# 20160708_DWC_LSM9DS1.net
KiCad netlist of a schematic drawn in EAGLE
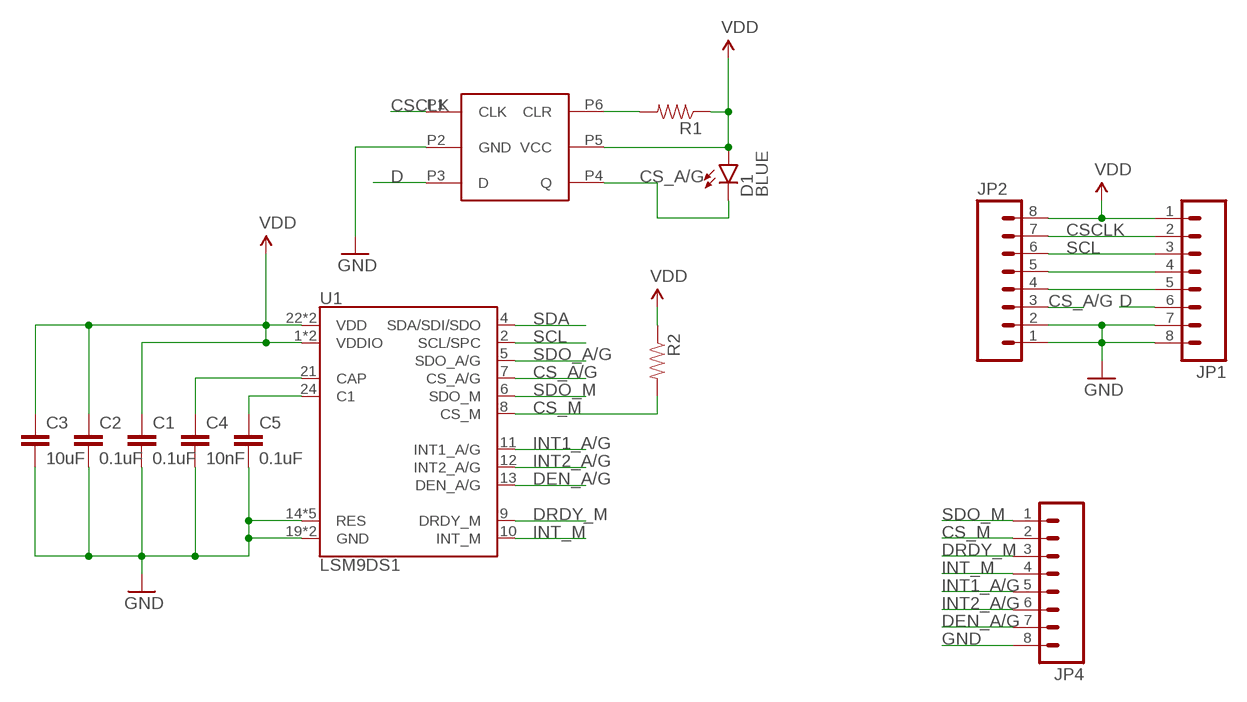
[diagram p0: schematic, sheet 1]

(export (version "E")
  (design (tool "Eeschema 10.0.6"))
  (components
    (comp (ref "C1")
      (value "0.1uF")
      (footprint "eagle-import:0603-CAP")
      (libsource (lib "eagle-import") (part "CAP0603-CAP"))
    )
    (comp (ref "C2")
      (value "0.1uF")
      (footprint "eagle-import:0603-CAP")
      (libsource (lib "eagle-import") (part "CAP0603-CAP"))
    )
    (comp (ref "C3")
      (value "10uF")
      (footprint "eagle-import:0603-CAP")
      (libsource (lib "eagle-import") (part "CAP0603-CAP"))
    )
    (comp (ref "C4")
      (value "10nF")
      (footprint "eagle-import:0603-CAP")
      (libsource (lib "eagle-import") (part "CAP0603-CAP"))
    )
    (comp (ref "C5")
      (value "0.1uF")
      (footprint "eagle-import:0603-CAP")
      (libsource (lib "eagle-import") (part "CAP0603-CAP"))
    )
    (comp (ref "D1")
      (value "BLUE")
      (footprint "eagle-import:LED-0603")
      (libsource (lib "eagle-import") (part "LED-BLUE0603"))
    )
    (comp (ref "JP1")
      (value "M08BM08B-SRSS-TB")
      (footprint "eagle-import:BM08B-SRSS-TB")
      (libsource (lib "eagle-import") (part "M08BM08B-SRSS-TB"))
    )
    (comp (ref "JP2")
      (value "M08BM08B-SRSS-TB")
      (footprint "eagle-import:BM08B-SRSS-TB")
      (libsource (lib "eagle-import") (part "M08BM08B-SRSS-TB"))
    )
    (comp (ref "JP4")
      (value "M08BM08B-SRSS-TB")
      (footprint "eagle-import:BM08B-SRSS-TB")
      (libsource (lib "eagle-import") (part "M08BM08B-SRSS-TB"))
    )
    (comp (ref "R1")
      (value "RESISTOR0603-RES")
      (footprint "eagle-import:0603-RES")
      (libsource (lib "eagle-import") (part "RESISTOR0603-RES"))
    )
    (comp (ref "R2")
      (value "RESISTOR0603-RES")
      (footprint "eagle-import:0603-RES")
      (libsource (lib "eagle-import") (part "RESISTOR0603-RES"))
    )
    (comp (ref "U$1")
      (value "SN74LVC1G175")
      (footprint "eagle-import:SN74LVC1G175")
      (libsource (lib "eagle-import") (part "SN74LVC1G175"))
    )
    (comp (ref "U1")
      (value "LSM9DS1")
      (footprint "eagle-import:LGA24-8X4")
      (libsource (lib "eagle-import") (part "LSM9DS1"))
    )
  )
  (nets
    (net (code "1") (name "/CSCLK") (class "Default")
      (node (ref "JP1") (pin "2") (pinfunction "2_2") (pintype "passive"))
      (node (ref "JP2") (pin "7") (pinfunction "7_7") (pintype "passive"))
      (node (ref "U$1") (pin "P1") (pinfunction "CLK_P1") (pintype "bidirectional"))
    )
    (net (code "2") (name "/CS_A{slash}G") (class "Default")
      (node (ref "D1") (pin "C") (pinfunction "C_C") (pintype "passive"))
      (node (ref "JP2") (pin "3") (pinfunction "3_3") (pintype "passive"))
      (node (ref "U$1") (pin "P4") (pinfunction "Q_P4") (pintype "bidirectional"))
      (node (ref "U1") (pin "7") (pinfunction "CS_A/G_7") (pintype "bidirectional"))
    )
    (net (code "3") (name "/CS_M") (class "Default")
      (node (ref "JP4") (pin "2") (pinfunction "2_2") (pintype "passive"))
      (node (ref "R2") (pin "2") (pinfunction "2_2") (pintype "passive"))
      (node (ref "U1") (pin "8") (pinfunction "CS_M_8") (pintype "bidirectional"))
    )
    (net (code "4") (name "/D") (class "Default")
      (node (ref "JP1") (pin "6") (pinfunction "6_6") (pintype "passive"))
      (node (ref "U$1") (pin "P3") (pinfunction "D_P3") (pintype "bidirectional"))
    )
    (net (code "5") (name "/DEN_A{slash}G") (class "Default")
      (node (ref "JP4") (pin "7") (pinfunction "7_7") (pintype "passive"))
      (node (ref "U1") (pin "13") (pinfunction "DEN_A/G_13") (pintype "bidirectional"))
    )
    (net (code "6") (name "/DRDY_M") (class "Default")
      (node (ref "JP4") (pin "3") (pinfunction "3_3") (pintype "passive"))
      (node (ref "U1") (pin "9") (pinfunction "DRDY_M_9") (pintype "bidirectional"))
    )
    (net (code "7") (name "/INT1_A{slash}G") (class "Default")
      (node (ref "JP4") (pin "5") (pinfunction "5_5") (pintype "passive"))
      (node (ref "U1") (pin "11") (pinfunction "INT1_A/G_11") (pintype "bidirectional"))
    )
    (net (code "8") (name "/INT2_A{slash}G") (class "Default")
      (node (ref "JP4") (pin "6") (pinfunction "6_6") (pintype "passive"))
      (node (ref "U1") (pin "12") (pinfunction "INT2_A/G_12") (pintype "bidirectional"))
    )
    (net (code "9") (name "/INT_M") (class "Default")
      (node (ref "JP4") (pin "4") (pinfunction "4_4") (pintype "passive"))
      (node (ref "U1") (pin "10") (pinfunction "INT_M_10") (pintype "bidirectional"))
    )
    (net (code "10") (name "/SCL") (class "Default")
      (node (ref "JP1") (pin "3") (pinfunction "3_3") (pintype "passive"))
      (node (ref "JP2") (pin "6") (pinfunction "6_6") (pintype "passive"))
      (node (ref "U1") (pin "2") (pinfunction "SCL/SPC_2") (pintype "bidirectional"))
    )
    (net (code "11") (name "/SDA") (class "Default")
      (node (ref "JP1") (pin "4") (pinfunction "4_4") (pintype "passive"))
      (node (ref "JP2") (pin "5") (pinfunction "5_5") (pintype "passive"))
      (node (ref "U1") (pin "4") (pinfunction "SDA/SDI/SDO_4") (pintype "bidirectional"))
    )
    (net (code "12") (name "/SDO_A{slash}G") (class "Default")
      (node (ref "JP1") (pin "5") (pinfunction "5_5") (pintype "passive"))
      (node (ref "JP2") (pin "4") (pinfunction "4_4") (pintype "passive"))
      (node (ref "U1") (pin "5") (pinfunction "SDO_A/G_5") (pintype "bidirectional"))
    )
    (net (code "13") (name "/SDO_M") (class "Default")
      (node (ref "JP4") (pin "1") (pinfunction "1_1") (pintype "passive"))
      (node (ref "U1") (pin "6") (pinfunction "SDO_M_6") (pintype "bidirectional"))
    )
    (net (code "14") (name "GND") (class "Default")
      (node (ref "C1") (pin "2") (pinfunction "2_2") (pintype "passive"))
      (node (ref "C2") (pin "2") (pinfunction "2_2") (pintype "passive"))
      (node (ref "C3") (pin "2") (pinfunction "2_2") (pintype "passive"))
      (node (ref "C4") (pin "2") (pinfunction "2_2") (pintype "passive"))
      (node (ref "C5") (pin "2") (pinfunction "2_2") (pintype "passive"))
      (node (ref "JP1") (pin "7") (pinfunction "7_7") (pintype "passive"))
      (node (ref "JP1") (pin "8") (pinfunction "8_8") (pintype "passive"))
      (node (ref "JP2") (pin "1") (pinfunction "1_1") (pintype "passive"))
      (node (ref "JP2") (pin "2") (pinfunction "2_2") (pintype "passive"))
      (node (ref "JP4") (pin "8") (pinfunction "8_8") (pintype "passive"))
      (node (ref "U$1") (pin "P2") (pinfunction "GND_P2") (pintype "bidirectional"))
      (node (ref "U1") (pin "14") (pinfunction "RES_14") (pintype "bidirectional"))
      (node (ref "U1") (pin "15") (pinfunction "RES_15") (pintype "bidirectional"))
      (node (ref "U1") (pin "16") (pinfunction "RES_16") (pintype "bidirectional"))
      (node (ref "U1") (pin "17") (pinfunction "RES_17") (pintype "bidirectional"))
      (node (ref "U1") (pin "18") (pinfunction "RES_18") (pintype "bidirectional"))
      (node (ref "U1") (pin "19") (pinfunction "GND_19") (pintype "bidirectional"))
      (node (ref "U1") (pin "20") (pinfunction "GND_20") (pintype "bidirectional"))
    )
    (net (code "15") (name "Net-(U$1-CLR)") (class "Default")
      (node (ref "R1") (pin "2") (pinfunction "2_2") (pintype "passive"))
      (node (ref "U$1") (pin "P6") (pinfunction "CLR_P6") (pintype "bidirectional"))
    )
    (net (code "16") (name "Net-(U1-C1)") (class "Default")
      (node (ref "C5") (pin "1") (pinfunction "1_1") (pintype "passive"))
      (node (ref "U1") (pin "24") (pinfunction "C1_24") (pintype "bidirectional"))
    )
    (net (code "17") (name "Net-(U1-CAP)") (class "Default")
      (node (ref "C4") (pin "1") (pinfunction "1_1") (pintype "passive"))
      (node (ref "U1") (pin "21") (pinfunction "CAP_21") (pintype "bidirectional"))
    )
    (net (code "18") (name "VDD") (class "Default")
      (node (ref "C1") (pin "1") (pinfunction "1_1") (pintype "passive"))
      (node (ref "C2") (pin "1") (pinfunction "1_1") (pintype "passive"))
      (node (ref "C3") (pin "1") (pinfunction "1_1") (pintype "passive"))
      (node (ref "D1") (pin "A") (pinfunction "A_A") (pintype "passive"))
      (node (ref "JP1") (pin "1") (pinfunction "1_1") (pintype "passive"))
      (node (ref "JP2") (pin "8") (pinfunction "8_8") (pintype "passive"))
      (node (ref "R1") (pin "1") (pinfunction "1_1") (pintype "passive"))
      (node (ref "R2") (pin "1") (pinfunction "1_1") (pintype "passive"))
      (node (ref "U$1") (pin "P5") (pinfunction "VCC_P5") (pintype "bidirectional"))
      (node (ref "U1") (pin "1") (pinfunction "VDDIO_1") (pintype "bidirectional"))
      (node (ref "U1") (pin "22") (pinfunction "VDD_22") (pintype "bidirectional"))
      (node (ref "U1") (pin "23") (pinfunction "VDD_23") (pintype "bidirectional"))
      (node (ref "U1") (pin "3") (pinfunction "VDDIO_3") (pintype "bidirectional"))
    )
  )
)
